# subckt_level_shifter.net
KiCad netlist of a schematic drawn in Altium Designer
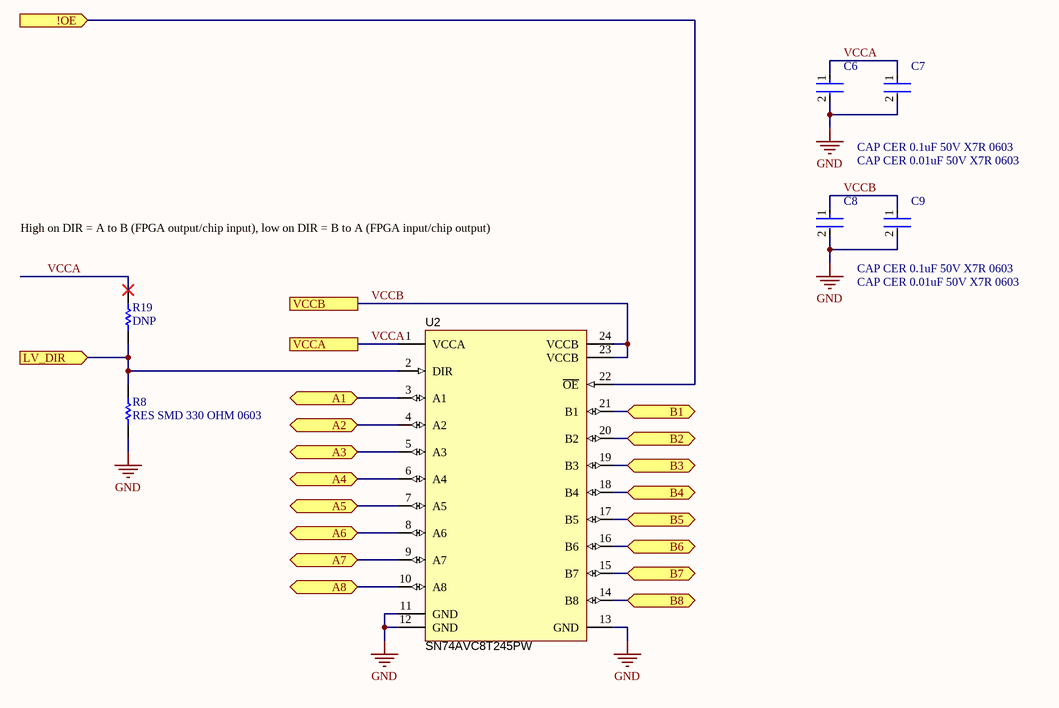
[diagram p0: subckt_level_shifter.SchDoc]

(export (version "E")
  (design (tool "Eeschema 10.0.6"))
  (components
    (comp (ref "C6")
      (value "CAP CER 0.1uF 50V X7R 0603")
      (footprint "FP-CC0603-DA-MFG")
      (fields
        (field (name "OCTOPART") "https://octopart.com/cc0603krx7r7bb104-yageo-192941")
        (field (name "TOLERANCE") "0.1")
        (field (name "VOLTAGE") "16 V")
      )
      (libsource (lib "Altium Content Vault") (part "11868f565c42a9108669ba33697ecf6"))
    )
    (comp (ref "C7")
      (value "CAP CER 0.01uF 50V X7R 0603")
      (footprint "FP-CC0603-DA-MFG")
      (fields
        (field (name "OCTOPART") "https://octopart.com/cc0603krx7r7bb104-yageo-192941")
        (field (name "TOLERANCE") "0.1")
        (field (name "VOLTAGE") "16 V")
      )
      (libsource (lib "Altium Content Vault") (part "11868f565c42a9108669ba33697ecf6"))
    )
    (comp (ref "C8")
      (value "CAP CER 0.1uF 50V X7R 0603")
      (footprint "FP-CC0603-DA-MFG")
      (fields
        (field (name "OCTOPART") "https://octopart.com/cc0603krx7r7bb104-yageo-192941")
        (field (name "TOLERANCE") "0.1")
        (field (name "VOLTAGE") "16 V")
      )
      (libsource (lib "Altium Content Vault") (part "11868f565c42a9108669ba33697ecf6"))
    )
    (comp (ref "C9")
      (value "CAP CER 0.01uF 50V X7R 0603")
      (footprint "FP-CC0603-DA-MFG")
      (fields
        (field (name "OCTOPART") "https://octopart.com/cc0603krx7r7bb104-yageo-192941")
        (field (name "TOLERANCE") "0.1")
        (field (name "VOLTAGE") "16 V")
      )
      (libsource (lib "Altium Content Vault") (part "11868f565c42a9108669ba33697ecf6"))
    )
    (comp (ref "R8")
      (value "RES SMD 330 OHM 0603")
      (footprint "RESC1609X50X30LL10T20")
      (fields (field (name "PART NUMBER") "CRCW0603100KFKEA") (field (name "MANUFACTURER") "Vishay Dale"))
      (libsource (lib "Altium Content Vault") (part "RES"))
    )
    (comp (ref "R19")
      (value "DNP")
      (footprint "RESC1609X50X30LL10T20")
      (fields (field (name "PART NUMBER") "CRCW0603100KFKEA") (field (name "MANUFACTURER") "Vishay Dale"))
      (libsource (lib "Altium Content Vault") (part "RES"))
    )
    (comp (ref "U2")
      (value "SN74AVC8T245PW")
      (footprint "PW0024A_N")
      (fields
        (field (name "MANUFACTURER") "Texas Instruments")
        (field (name "SYMBOLCREATOR") "a0411947")
        (field (name "PUBLISHER") "Texas Instruments")
      )
      (libsource (lib "TIDA-00172_revE2") (part "SN74AVC8T245PW"))
    )
  )
  (nets
    (net (code "1") (name "/!OE") (class "Default")
      (node (ref "U2") (pin "22") (pinfunction "OE_22") (pintype "input"))
    )
    (net (code "2") (name "/A1") (class "Default")
      (node (ref "U2") (pin "3") (pinfunction "A1_3") (pintype "bidirectional"))
    )
    (net (code "3") (name "/A2") (class "Default")
      (node (ref "U2") (pin "4") (pinfunction "A2_4") (pintype "bidirectional"))
    )
    (net (code "4") (name "/A3") (class "Default")
      (node (ref "U2") (pin "5") (pinfunction "A3_5") (pintype "bidirectional"))
    )
    (net (code "5") (name "/A4") (class "Default")
      (node (ref "U2") (pin "6") (pinfunction "A4_6") (pintype "bidirectional"))
    )
    (net (code "6") (name "/A5") (class "Default")
      (node (ref "U2") (pin "7") (pinfunction "A5_7") (pintype "bidirectional"))
    )
    (net (code "7") (name "/A6") (class "Default")
      (node (ref "U2") (pin "8") (pinfunction "A6_8") (pintype "bidirectional"))
    )
    (net (code "8") (name "/A7") (class "Default")
      (node (ref "U2") (pin "9") (pinfunction "A7_9") (pintype "bidirectional"))
    )
    (net (code "9") (name "/A8") (class "Default")
      (node (ref "U2") (pin "10") (pinfunction "A8_10") (pintype "bidirectional"))
    )
    (net (code "10") (name "/B1") (class "Default")
      (node (ref "U2") (pin "21") (pinfunction "B1_21") (pintype "bidirectional"))
    )
    (net (code "11") (name "/B2") (class "Default")
      (node (ref "U2") (pin "20") (pinfunction "B2_20") (pintype "bidirectional"))
    )
    (net (code "12") (name "/B3") (class "Default")
      (node (ref "U2") (pin "19") (pinfunction "B3_19") (pintype "bidirectional"))
    )
    (net (code "13") (name "/B4") (class "Default")
      (node (ref "U2") (pin "18") (pinfunction "B4_18") (pintype "bidirectional"))
    )
    (net (code "14") (name "/B5") (class "Default")
      (node (ref "U2") (pin "17") (pinfunction "B5_17") (pintype "bidirectional"))
    )
    (net (code "15") (name "/B6") (class "Default")
      (node (ref "U2") (pin "16") (pinfunction "B6_16") (pintype "bidirectional"))
    )
    (net (code "16") (name "/B7") (class "Default")
      (node (ref "U2") (pin "15") (pinfunction "B7_15") (pintype "bidirectional"))
    )
    (net (code "17") (name "/B8") (class "Default")
      (node (ref "U2") (pin "14") (pinfunction "B8_14") (pintype "bidirectional"))
    )
    (net (code "18") (name "/LV_DIR") (class "Default")
      (node (ref "R19") (pin "2") (pinfunction "2_2") (pintype "passive"))
      (node (ref "R8") (pin "1") (pinfunction "1_1") (pintype "passive"))
      (node (ref "U2") (pin "2") (pinfunction "DIR_2") (pintype "input"))
    )
    (net (code "19") (name "/VCCA") (class "Default")
      (node (ref "C6") (pin "1") (pinfunction "1_1") (pintype "passive"))
      (node (ref "C7") (pin "1") (pinfunction "1_1") (pintype "passive"))
      (node (ref "R19") (pin "1") (pinfunction "1_1") (pintype "passive"))
      (node (ref "U2") (pin "1") (pinfunction "VCCA_1") (pintype "power_in"))
    )
    (net (code "20") (name "/VCCB") (class "Default")
      (node (ref "C8") (pin "1") (pinfunction "1_1") (pintype "passive"))
      (node (ref "C9") (pin "1") (pinfunction "1_1") (pintype "passive"))
      (node (ref "U2") (pin "23") (pinfunction "VCCB_23") (pintype "power_in"))
      (node (ref "U2") (pin "24") (pinfunction "VCCB_24") (pintype "power_in"))
    )
    (net (code "21") (name "GND") (class "Default")
      (node (ref "C6") (pin "2") (pinfunction "2_2") (pintype "passive"))
      (node (ref "C7") (pin "2") (pinfunction "2_2") (pintype "passive"))
      (node (ref "C8") (pin "2") (pinfunction "2_2") (pintype "passive"))
      (node (ref "C9") (pin "2") (pinfunction "2_2") (pintype "passive"))
      (node (ref "R8") (pin "2") (pinfunction "2_2") (pintype "passive"))
      (node (ref "U2") (pin "11") (pinfunction "GND_11") (pintype "power_in"))
      (node (ref "U2") (pin "12") (pinfunction "GND_12") (pintype "power_in"))
      (node (ref "U2") (pin "13") (pinfunction "GND_13") (pintype "power_in"))
    )
  )
)
